# Sch_Action.net
KiCad netlist of a schematic drawn in Altium Designer
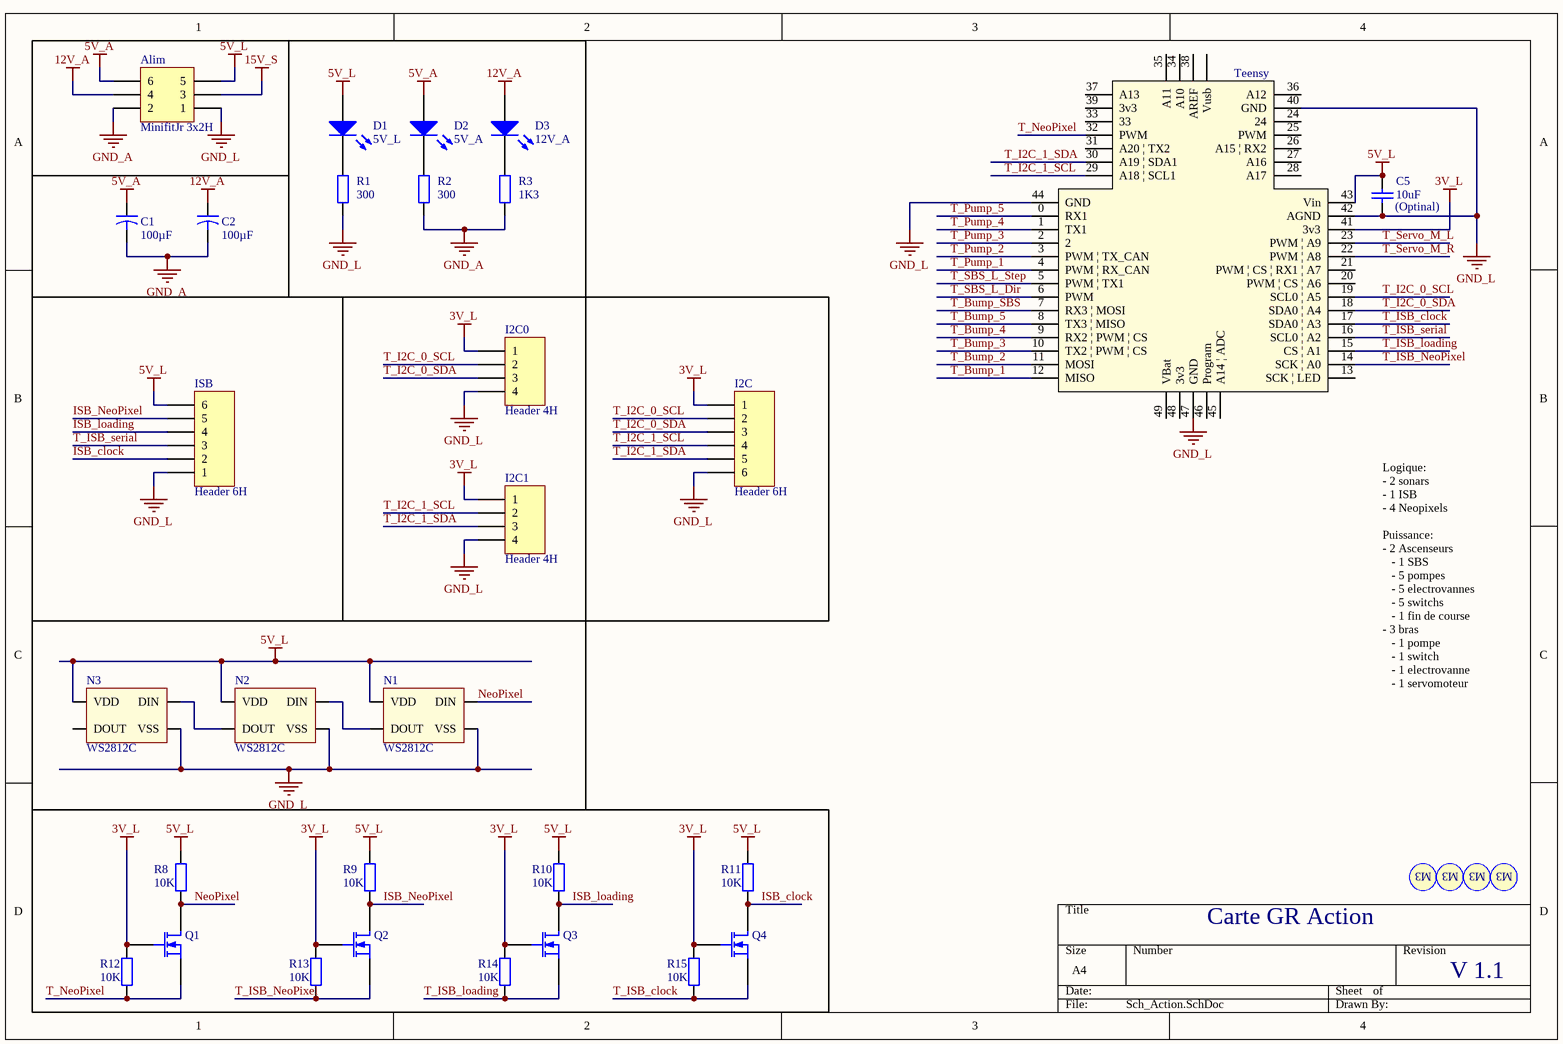
[diagram p0: Sch_Action.SchDoc]

(export (version "E")
  (design (tool "Eeschema 10.0.6"))
  (components
    (comp (ref "Alim")
      (value "MinifitJr 3x2H")
      (footprint "MOLEX_MINIFITJR_3X2")
      (description "Header, 3-Pin, Dual row, Right Angle")
      (fields (field (name "PUBLISHER") "Altium Limited"))
      (libsource (lib "Miscellaneous Connectors") (part "Header 3X2H"))
    )
    (comp (ref "C1")
      (value "100µF")
      (footprint "Condensateur")
      (description "Capacitor")
      (fields (field (name "Comment") "Cap2") (field (name "PUBLISHER") "Altium Limited"))
      (libsource (lib "Miscellaneous Devices") (part "Cap2"))
    )
    (comp (ref "C2")
      (value "100µF")
      (footprint "Condensateur")
      (description "Capacitor")
      (fields (field (name "Comment") "Cap2") (field (name "PUBLISHER") "Altium Limited"))
      (libsource (lib "Miscellaneous Devices") (part "Cap2"))
    )
    (comp (ref "C5")
      (value "(Optinal)")
      (footprint "Capacitor 1206")
      (description "Capacitor")
      (fields (field (name "ALTIUM_VALUE") "10uF") (field (name "PUBLISHER") "Altium Limited"))
      (libsource (lib "Miscellaneous Devices") (part "Cap"))
    )
    (comp (ref "D1")
      (value "5V_L")
      (footprint "KP-3216SEC")
      (description "Typical RED, GREEN, YELLOW, AMBER GaAs LED")
      (fields (field (name "PUBLISHER") "Altium Limited"))
      (libsource (lib "Miscellaneous Devices") (part "LED2"))
    )
    (comp (ref "D2")
      (value "5V_A")
      (footprint "KP-3216SEC")
      (description "Typical RED, GREEN, YELLOW, AMBER GaAs LED")
      (fields (field (name "PUBLISHER") "Altium Limited"))
      (libsource (lib "Miscellaneous Devices") (part "LED2"))
    )
    (comp (ref "D3")
      (value "12V_A")
      (footprint "KP-3216SEC")
      (description "Typical RED, GREEN, YELLOW, AMBER GaAs LED")
      (fields (field (name "PUBLISHER") "Altium Limited"))
      (libsource (lib "Miscellaneous Devices") (part "LED2"))
    )
    (comp (ref "I2C")
      (value "Header 6H")
      (footprint "S6B-XH-A")
      (description "Header, 6-Pin, Right Angle")
      (fields (field (name "PUBLISHER") "Altium Limited"))
      (libsource (lib "") (part "Header 6H_1"))
    )
    (comp (ref "I2C0")
      (value "Header 4H")
      (footprint "S4B-XH-A")
      (description "Header, 4-Pin, Right Angle")
      (fields (field (name "PUBLISHER") "Altium Limited"))
      (libsource (lib "Miscellaneous Connectors") (part "Header 4H"))
    )
    (comp (ref "I2C1")
      (value "Header 4H")
      (footprint "S4B-XH-A")
      (description "Header, 4-Pin, Right Angle")
      (fields (field (name "PUBLISHER") "Altium Limited"))
      (libsource (lib "Miscellaneous Connectors") (part "Header 4H"))
    )
    (comp (ref "ISB")
      (value "Header 6H")
      (footprint "S6B-XH-A")
      (description "Header, 6-Pin, Right Angle")
      (fields (field (name "PUBLISHER") "Altium Limited"))
      (libsource (lib "Miscellaneous Connectors") (part "Header 6H"))
    )
    (comp (ref "N1")
      (value "WS2812C")
      (footprint "WS2812C")
      (description "Intelligent control LED")
      (libsource (lib "Robot_2020") (part "WS2812C"))
    )
    (comp (ref "N2")
      (value "WS2812C")
      (footprint "WS2812C")
      (description "Intelligent control LED")
      (libsource (lib "Robot_2020") (part "WS2812C"))
    )
    (comp (ref "N3")
      (value "WS2812C")
      (footprint "WS2812C")
      (description "Intelligent control LED")
      (libsource (lib "Robot_2020") (part "WS2812C"))
    )
    (comp (ref "Q1")
      (value "MOSFET-N")
      (footprint "SOT23_M")
      (description "N-Channel MOSFET")
      (fields (field (name "PUBLISHER") "Altium Limited"))
      (libsource (lib "Miscellaneous Devices") (part "MOSFET-N"))
    )
    (comp (ref "Q2")
      (value "MOSFET-N")
      (footprint "SOT23_M")
      (description "N-Channel MOSFET")
      (fields (field (name "PUBLISHER") "Altium Limited"))
      (libsource (lib "Miscellaneous Devices") (part "MOSFET-N"))
    )
    (comp (ref "Q3")
      (value "MOSFET-N")
      (footprint "SOT23_M")
      (description "N-Channel MOSFET")
      (fields (field (name "PUBLISHER") "Altium Limited"))
      (libsource (lib "Miscellaneous Devices") (part "MOSFET-N"))
    )
    (comp (ref "Q4")
      (value "MOSFET-N")
      (footprint "SOT23_M")
      (description "N-Channel MOSFET")
      (fields (field (name "PUBLISHER") "Altium Limited"))
      (libsource (lib "Miscellaneous Devices") (part "MOSFET-N"))
    )
    (comp (ref "R1")
      (value "300")
      (footprint "Resistor 1206")
      (description "Resistor")
      (fields (field (name "Comment") "Res2") (field (name "PUBLISHER") "Altium Limited"))
      (libsource (lib "") (part "Res2_1"))
    )
    (comp (ref "R2")
      (value "300")
      (footprint "Resistor 1206")
      (description "Resistor")
      (fields (field (name "Comment") "Res2") (field (name "PUBLISHER") "Altium Limited"))
      (libsource (lib "Miscellaneous Devices") (part "Res2"))
    )
    (comp (ref "R3")
      (value "1K3")
      (footprint "Resistor 1206")
      (description "Resistor")
      (fields (field (name "Comment") "Res2") (field (name "PUBLISHER") "Altium Limited"))
      (libsource (lib "Miscellaneous Devices") (part "Res2"))
    )
    (comp (ref "R8")
      (value "10K")
      (footprint "Resistor 1206")
      (description "Resistor")
      (fields (field (name "Comment") "Res2") (field (name "PUBLISHER") "Altium Limited"))
      (libsource (lib "") (part "Res2_1"))
    )
    (comp (ref "R9")
      (value "10K")
      (footprint "Resistor 1206")
      (description "Resistor")
      (fields (field (name "Comment") "Res2") (field (name "PUBLISHER") "Altium Limited"))
      (libsource (lib "") (part "Res2_1"))
    )
    (comp (ref "R10")
      (value "10K")
      (footprint "Resistor 1206")
      (description "Resistor")
      (fields (field (name "Comment") "Res2") (field (name "PUBLISHER") "Altium Limited"))
      (libsource (lib "") (part "Res2_1"))
    )
    (comp (ref "R11")
      (value "10K")
      (footprint "Resistor 1206")
      (description "Resistor")
      (fields (field (name "Comment") "Res2") (field (name "PUBLISHER") "Altium Limited"))
      (libsource (lib "") (part "Res2_1"))
    )
    (comp (ref "R12")
      (value "10K")
      (footprint "Resistor 1206")
      (description "Resistor")
      (fields (field (name "Comment") "Res2") (field (name "PUBLISHER") "Altium Limited"))
      (libsource (lib "") (part "Res2_1"))
    )
    (comp (ref "R13")
      (value "10K")
      (footprint "Resistor 1206")
      (description "Resistor")
      (fields (field (name "Comment") "Res2") (field (name "PUBLISHER") "Altium Limited"))
      (libsource (lib "") (part "Res2_1"))
    )
    (comp (ref "R14")
      (value "10K")
      (footprint "Resistor 1206")
      (description "Resistor")
      (fields (field (name "Comment") "Res2") (field (name "PUBLISHER") "Altium Limited"))
      (libsource (lib "") (part "Res2_1"))
    )
    (comp (ref "R15")
      (value "10K")
      (footprint "Resistor 1206")
      (description "Resistor")
      (fields (field (name "Comment") "Res2") (field (name "PUBLISHER") "Altium Limited"))
      (libsource (lib "") (part "Res2_1"))
    )
    (comp (ref "S1")
      (value "Screw M3")
      (footprint "Screw M3")
      (libsource (lib "Robot_2020") (part "Screw M3"))
    )
    (comp (ref "S2")
      (value "Screw M3")
      (footprint "Screw M3")
      (libsource (lib "Robot_2020") (part "Screw M3"))
    )
    (comp (ref "S3")
      (value "Screw M3")
      (footprint "Screw M3")
      (libsource (lib "Robot_2020") (part "Screw M3"))
    )
    (comp (ref "S4")
      (value "Screw M3")
      (footprint "Screw M3")
      (libsource (lib "Robot_2020") (part "Screw M3"))
    )
    (comp (ref "Teensy")
      (value "Teensy 3.2")
      (footprint "teensy")
      (libsource (lib "Robot_2020") (part "teensy3.2"))
    )
  )
  (nets
    (net (code "1") (name "/ISB_NeoPixel") (class "Default")
      (node (ref "ISB") (pin "5") (pinfunction "5_5") (pintype "passive"))
      (node (ref "Q2") (pin "1") (pinfunction "D_1") (pintype "passive"))
      (node (ref "R9") (pin "1") (pinfunction "1_1") (pintype "passive"))
    )
    (net (code "2") (name "/ISB_clock") (class "Default")
      (node (ref "ISB") (pin "2") (pinfunction "2_2") (pintype "passive"))
      (node (ref "Q4") (pin "1") (pinfunction "D_1") (pintype "passive"))
      (node (ref "R11") (pin "1") (pinfunction "1_1") (pintype "passive"))
    )
    (net (code "3") (name "/ISB_loading") (class "Default")
      (node (ref "ISB") (pin "4") (pinfunction "4_4") (pintype "passive"))
      (node (ref "Q3") (pin "1") (pinfunction "D_1") (pintype "passive"))
      (node (ref "R10") (pin "1") (pinfunction "1_1") (pintype "passive"))
    )
    (net (code "4") (name "/NeoPixel") (class "Default")
      (node (ref "N1") (pin "4") (pinfunction "DIN_4") (pintype "passive"))
      (node (ref "Q1") (pin "1") (pinfunction "D_1") (pintype "passive"))
      (node (ref "R8") (pin "1") (pinfunction "1_1") (pintype "passive"))
    )
    (net (code "5") (name "/T_Bump_1") (class "Default")
      (node (ref "Teensy") (pin "12") (pinfunction "MISO_12") (pintype "passive"))
    )
    (net (code "6") (name "/T_Bump_2") (class "Default")
      (node (ref "Teensy") (pin "11") (pinfunction "MOSI_11") (pintype "passive"))
    )
    (net (code "7") (name "/T_Bump_3") (class "Default")
      (node (ref "Teensy") (pin "10") (pinfunction "TX2_¦_PWM_¦_CS_10") (pintype "passive"))
    )
    (net (code "8") (name "/T_Bump_4") (class "Default")
      (node (ref "Teensy") (pin "9") (pinfunction "RX2_¦_PWM_¦_CS_9") (pintype "passive"))
    )
    (net (code "9") (name "/T_Bump_5") (class "Default")
      (node (ref "Teensy") (pin "8") (pinfunction "TX3_¦_MISO_8") (pintype "passive"))
    )
    (net (code "10") (name "/T_Bump_SBS") (class "Default")
      (node (ref "Teensy") (pin "7") (pinfunction "RX3_¦_MOSI_7") (pintype "passive"))
    )
    (net (code "11") (name "/T_I2C_0_SCL") (class "Default")
      (node (ref "I2C") (pin "2") (pinfunction "2_2") (pintype "passive"))
      (node (ref "I2C0") (pin "2") (pinfunction "2_2") (pintype "passive"))
      (node (ref "Teensy") (pin "19") (pinfunction "SCL0_¦_A5_19") (pintype "passive"))
    )
    (net (code "12") (name "/T_I2C_0_SDA") (class "Default")
      (node (ref "I2C") (pin "3") (pinfunction "3_3") (pintype "passive"))
      (node (ref "I2C0") (pin "3") (pinfunction "3_3") (pintype "passive"))
      (node (ref "Teensy") (pin "18") (pinfunction "SDA0_¦_A4_18") (pintype "passive"))
    )
    (net (code "13") (name "/T_I2C_1_SCL") (class "Default")
      (node (ref "I2C") (pin "4") (pinfunction "4_4") (pintype "passive"))
      (node (ref "I2C1") (pin "2") (pinfunction "2_2") (pintype "passive"))
      (node (ref "Teensy") (pin "29") (pinfunction "A18_¦_SCL1_29") (pintype "passive"))
    )
    (net (code "14") (name "/T_I2C_1_SDA") (class "Default")
      (node (ref "I2C") (pin "5") (pinfunction "5_5") (pintype "passive"))
      (node (ref "I2C1") (pin "3") (pinfunction "3_3") (pintype "passive"))
      (node (ref "Teensy") (pin "30") (pinfunction "A19_¦_SDA1_30") (pintype "passive"))
    )
    (net (code "15") (name "/T_ISB_NeoPixel") (class "Default")
      (node (ref "Q2") (pin "3") (pinfunction "S_3") (pintype "passive"))
      (node (ref "R13") (pin "1") (pinfunction "1_1") (pintype "passive"))
      (node (ref "Teensy") (pin "14") (pinfunction "SCK_¦_A0_14") (pintype "passive"))
    )
    (net (code "16") (name "/T_ISB_clock") (class "Default")
      (node (ref "Q4") (pin "3") (pinfunction "S_3") (pintype "passive"))
      (node (ref "R15") (pin "1") (pinfunction "1_1") (pintype "passive"))
      (node (ref "Teensy") (pin "17") (pinfunction "SDA0_¦_A3_17") (pintype "passive"))
    )
    (net (code "17") (name "/T_ISB_loading") (class "Default")
      (node (ref "Q3") (pin "3") (pinfunction "S_3") (pintype "passive"))
      (node (ref "R14") (pin "1") (pinfunction "1_1") (pintype "passive"))
      (node (ref "Teensy") (pin "15") (pinfunction "CS_¦_A1_15") (pintype "passive"))
    )
    (net (code "18") (name "/T_ISB_serial") (class "Default")
      (node (ref "ISB") (pin "3") (pinfunction "3_3") (pintype "passive"))
      (node (ref "Teensy") (pin "16") (pinfunction "SCL0_¦_A2_16") (pintype "passive"))
    )
    (net (code "19") (name "/T_NeoPixel") (class "Default")
      (node (ref "Q1") (pin "3") (pinfunction "S_3") (pintype "passive"))
      (node (ref "R12") (pin "1") (pinfunction "1_1") (pintype "passive"))
      (node (ref "Teensy") (pin "32") (pinfunction "PWM_32") (pintype "passive"))
    )
    (net (code "20") (name "/T_Pump_1") (class "Default")
      (node (ref "Teensy") (pin "4") (pinfunction "PWM_¦_RX_CAN_4") (pintype "passive"))
    )
    (net (code "21") (name "/T_Pump_2") (class "Default")
      (node (ref "Teensy") (pin "3") (pinfunction "PWM_¦_TX_CAN_3") (pintype "passive"))
    )
    (net (code "22") (name "/T_Pump_3") (class "Default")
      (node (ref "Teensy") (pin "2") (pinfunction "2_2") (pintype "passive"))
    )
    (net (code "23") (name "/T_Pump_4") (class "Default")
      (node (ref "Teensy") (pin "1") (pinfunction "TX1_1") (pintype "passive"))
    )
    (net (code "24") (name "/T_Pump_5") (class "Default")
      (node (ref "Teensy") (pin "0") (pinfunction "RX1_0") (pintype "passive"))
    )
    (net (code "25") (name "/T_SBS_L_Dir") (class "Default")
      (node (ref "Teensy") (pin "6") (pinfunction "PWM_6") (pintype "passive"))
    )
    (net (code "26") (name "/T_SBS_L_Step") (class "Default")
      (node (ref "Teensy") (pin "5") (pinfunction "PWM_¦_TX1_5") (pintype "passive"))
    )
    (net (code "27") (name "/T_Servo_M_L") (class "Default")
      (node (ref "Teensy") (pin "23") (pinfunction "PWM_¦_A9_23") (pintype "passive"))
    )
    (net (code "28") (name "/T_Servo_M_R") (class "Default")
      (node (ref "Teensy") (pin "22") (pinfunction "PWM_¦_A8_22") (pintype "passive"))
    )
    (net (code "29") (name "3V_L") (class "Default")
      (node (ref "I2C") (pin "1") (pinfunction "1_1") (pintype "passive"))
      (node (ref "I2C0") (pin "1") (pinfunction "1_1") (pintype "passive"))
      (node (ref "I2C1") (pin "1") (pinfunction "1_1") (pintype "passive"))
      (node (ref "Q1") (pin "2") (pinfunction "G_2") (pintype "passive"))
      (node (ref "Q2") (pin "2") (pinfunction "G_2") (pintype "passive"))
      (node (ref "Q3") (pin "2") (pinfunction "G_2") (pintype "passive"))
      (node (ref "Q4") (pin "2") (pinfunction "G_2") (pintype "passive"))
      (node (ref "R12") (pin "2") (pinfunction "2_2") (pintype "passive"))
      (node (ref "R13") (pin "2") (pinfunction "2_2") (pintype "passive"))
      (node (ref "R14") (pin "2") (pinfunction "2_2") (pintype "passive"))
      (node (ref "R15") (pin "2") (pinfunction "2_2") (pintype "passive"))
      (node (ref "Teensy") (pin "41") (pinfunction "3v3_41") (pintype "passive"))
    )
    (net (code "30") (name "5V_A") (class "Default")
      (node (ref "Alim") (pin "6") (pinfunction "6_6") (pintype "passive"))
      (node (ref "C1") (pin "1") (pinfunction "1_1") (pintype "passive"))
      (node (ref "D2") (pin "1") (pinfunction "A_1") (pintype "passive"))
    )
    (net (code "31") (name "5V_L") (class "Default")
      (node (ref "Alim") (pin "5") (pinfunction "5_5") (pintype "passive"))
      (node (ref "C5") (pin "2") (pinfunction "2_2") (pintype "passive"))
      (node (ref "D1") (pin "1") (pinfunction "A_1") (pintype "passive"))
      (node (ref "ISB") (pin "6") (pinfunction "6_6") (pintype "passive"))
      (node (ref "N1") (pin "1") (pinfunction "VDD_1") (pintype "passive"))
      (node (ref "N2") (pin "1") (pinfunction "VDD_1") (pintype "passive"))
      (node (ref "N3") (pin "1") (pinfunction "VDD_1") (pintype "passive"))
      (node (ref "R10") (pin "2") (pinfunction "2_2") (pintype "passive"))
      (node (ref "R11") (pin "2") (pinfunction "2_2") (pintype "passive"))
      (node (ref "R8") (pin "2") (pinfunction "2_2") (pintype "passive"))
      (node (ref "R9") (pin "2") (pinfunction "2_2") (pintype "passive"))
      (node (ref "Teensy") (pin "43") (pinfunction "Vin_43") (pintype "passive"))
    )
    (net (code "32") (name "12V_A") (class "Default")
      (node (ref "Alim") (pin "4") (pinfunction "4_4") (pintype "passive"))
      (node (ref "C2") (pin "1") (pinfunction "1_1") (pintype "passive"))
      (node (ref "D3") (pin "1") (pinfunction "A_1") (pintype "passive"))
    )
    (net (code "33") (name "15V_S") (class "Default")
      (node (ref "Alim") (pin "3") (pinfunction "3_3") (pintype "passive"))
    )
    (net (code "34") (name "GND_A") (class "Default")
      (node (ref "Alim") (pin "2") (pinfunction "2_2") (pintype "passive"))
      (node (ref "C1") (pin "2") (pinfunction "2_2") (pintype "passive"))
      (node (ref "C2") (pin "2") (pinfunction "2_2") (pintype "passive"))
      (node (ref "R2") (pin "2") (pinfunction "2_2") (pintype "passive"))
      (node (ref "R3") (pin "2") (pinfunction "2_2") (pintype "passive"))
    )
    (net (code "35") (name "GND_L") (class "Default")
      (node (ref "Alim") (pin "1") (pinfunction "1_1") (pintype "passive"))
      (node (ref "C5") (pin "1") (pinfunction "1_1") (pintype "passive"))
      (node (ref "I2C") (pin "6") (pinfunction "6_6") (pintype "passive"))
      (node (ref "I2C0") (pin "4") (pinfunction "4_4") (pintype "passive"))
      (node (ref "I2C1") (pin "4") (pinfunction "4_4") (pintype "passive"))
      (node (ref "ISB") (pin "1") (pinfunction "1_1") (pintype "passive"))
      (node (ref "N1") (pin "3") (pinfunction "VSS_3") (pintype "passive"))
      (node (ref "N2") (pin "3") (pinfunction "VSS_3") (pintype "passive"))
      (node (ref "N3") (pin "3") (pinfunction "VSS_3") (pintype "passive"))
      (node (ref "R1") (pin "1") (pinfunction "1_1") (pintype "passive"))
      (node (ref "Teensy") (pin "40") (pinfunction "GND_40") (pintype "passive"))
      (node (ref "Teensy") (pin "42") (pinfunction "AGND_42") (pintype "passive"))
      (node (ref "Teensy") (pin "44") (pinfunction "GND_44") (pintype "passive"))
      (node (ref "Teensy") (pin "47") (pinfunction "GND_47") (pintype "passive"))
    )
    (net (code "36") (name "Net-(D1-K)") (class "Default")
      (node (ref "D1") (pin "2") (pinfunction "K_2") (pintype "passive"))
      (node (ref "R1") (pin "2") (pinfunction "2_2") (pintype "passive"))
    )
    (net (code "37") (name "Net-(D2-K)") (class "Default")
      (node (ref "D2") (pin "2") (pinfunction "K_2") (pintype "passive"))
      (node (ref "R2") (pin "1") (pinfunction "1_1") (pintype "passive"))
    )
    (net (code "38") (name "Net-(D3-K)") (class "Default")
      (node (ref "D3") (pin "2") (pinfunction "K_2") (pintype "passive"))
      (node (ref "R3") (pin "1") (pinfunction "1_1") (pintype "passive"))
    )
    (net (code "39") (name "Net-(N1-DOUT)") (class "Default")
      (node (ref "N1") (pin "2") (pinfunction "DOUT_2") (pintype "passive"))
      (node (ref "N2") (pin "4") (pinfunction "DIN_4") (pintype "passive"))
    )
    (net (code "40") (name "Net-(N2-DOUT)") (class "Default")
      (node (ref "N2") (pin "2") (pinfunction "DOUT_2") (pintype "passive"))
      (node (ref "N3") (pin "4") (pinfunction "DIN_4") (pintype "passive"))
    )
    (net (code "41") (name "unconnected-(N3-DOUT-Pad2)") (class "Default")
      (node (ref "N3") (pin "2") (pinfunction "DOUT_2") (pintype "passive"))
    )
    (net (code "42") (name "unconnected-(Teensy-3v3-Pad39)") (class "Default")
      (node (ref "Teensy") (pin "39") (pinfunction "3v3_39") (pintype "passive"))
    )
    (net (code "43") (name "unconnected-(Teensy-3v3-Pad48)") (class "Default")
      (node (ref "Teensy") (pin "48") (pinfunction "3v3_48") (pintype "passive"))
    )
    (net (code "44") (name "unconnected-(Teensy-A10-Pad34)") (class "Default")
      (node (ref "Teensy") (pin "34") (pinfunction "A10_34") (pintype "passive"))
    )
    (net (code "45") (name "unconnected-(Teensy-A11-Pad35)") (class "Default")
      (node (ref "Teensy") (pin "35") (pinfunction "A11_35") (pintype "passive"))
    )
    (net (code "46") (name "unconnected-(Teensy-A12-Pad36)") (class "Default")
      (node (ref "Teensy") (pin "36") (pinfunction "A12_36") (pintype "passive"))
    )
    (net (code "47") (name "unconnected-(Teensy-A13-Pad37)") (class "Default")
      (node (ref "Teensy") (pin "37") (pinfunction "A13_37") (pintype "passive"))
    )
    (net (code "48") (name "unconnected-(Teensy-A14_¦_ADC-Pad45)") (class "Default")
      (node (ref "Teensy") (pin "45") (pinfunction "A14_¦_ADC_45") (pintype "passive"))
    )
    (net (code "49") (name "unconnected-(Teensy-A15_¦_RX2-Pad26)") (class "Default")
      (node (ref "Teensy") (pin "26") (pinfunction "A15_¦_RX2_26") (pintype "passive"))
    )
    (net (code "50") (name "unconnected-(Teensy-A16-Pad27)") (class "Default")
      (node (ref "Teensy") (pin "27") (pinfunction "A16_27") (pintype "passive"))
    )
    (net (code "51") (name "unconnected-(Teensy-A17-Pad28)") (class "Default")
      (node (ref "Teensy") (pin "28") (pinfunction "A17_28") (pintype "passive"))
    )
    (net (code "52") (name "unconnected-(Teensy-A20_¦_TX2-Pad31)") (class "Default")
      (node (ref "Teensy") (pin "31") (pinfunction "A20_¦_TX2_31") (pintype "passive"))
    )
    (net (code "53") (name "unconnected-(Teensy-AREF-Pad38)") (class "Default")
      (node (ref "Teensy") (pin "38") (pinfunction "AREF_38") (pintype "passive"))
    )
    (net (code "54") (name "unconnected-(Teensy-PWM-Pad25)") (class "Default")
      (node (ref "Teensy") (pin "25") (pinfunction "PWM_25") (pintype "passive"))
    )
    (net (code "55") (name "unconnected-(Teensy-PWM_¦_CS_¦_A6-Pad20)") (class "Default")
      (node (ref "Teensy") (pin "20") (pinfunction "PWM_¦_CS_¦_A6_20") (pintype "passive"))
    )
    (net (code "56") (name "unconnected-(Teensy-PWM_¦_CS_¦_RX1_¦_A7-Pad21)") (class "Default")
      (node (ref "Teensy") (pin "21") (pinfunction "PWM_¦_CS_¦_RX1_¦_A7_21") (pintype "passive"))
    )
    (net (code "57") (name "unconnected-(Teensy-Pad24)") (class "Default")
      (node (ref "Teensy") (pin "24") (pinfunction "24_24") (pintype "passive"))
    )
    (net (code "58") (name "unconnected-(Teensy-Pad33)") (class "Default")
      (node (ref "Teensy") (pin "33") (pinfunction "33_33") (pintype "passive"))
    )
    (net (code "59") (name "unconnected-(Teensy-Program-Pad46)") (class "Default")
      (node (ref "Teensy") (pin "46") (pinfunction "Program_46") (pintype "passive"))
    )
    (net (code "60") (name "unconnected-(Teensy-SCK_¦_LED-Pad13)") (class "Default")
      (node (ref "Teensy") (pin "13") (pinfunction "SCK_¦_LED_13") (pintype "passive"))
    )
    (net (code "61") (name "unconnected-(Teensy-VBat-Pad49)") (class "Default")
      (node (ref "Teensy") (pin "49") (pinfunction "VBat_49") (pintype "passive"))
    )
    (net (code "62") (name "unconnected-(Teensy-Vusb-Pad50)") (class "Default")
      (node (ref "Teensy") (pin "50") (pinfunction "Vusb_50") (pintype "passive"))
    )
  )
)
